# unicorder-mk-1_3-base.net
KiCad netlist of a schematic drawn in EAGLE
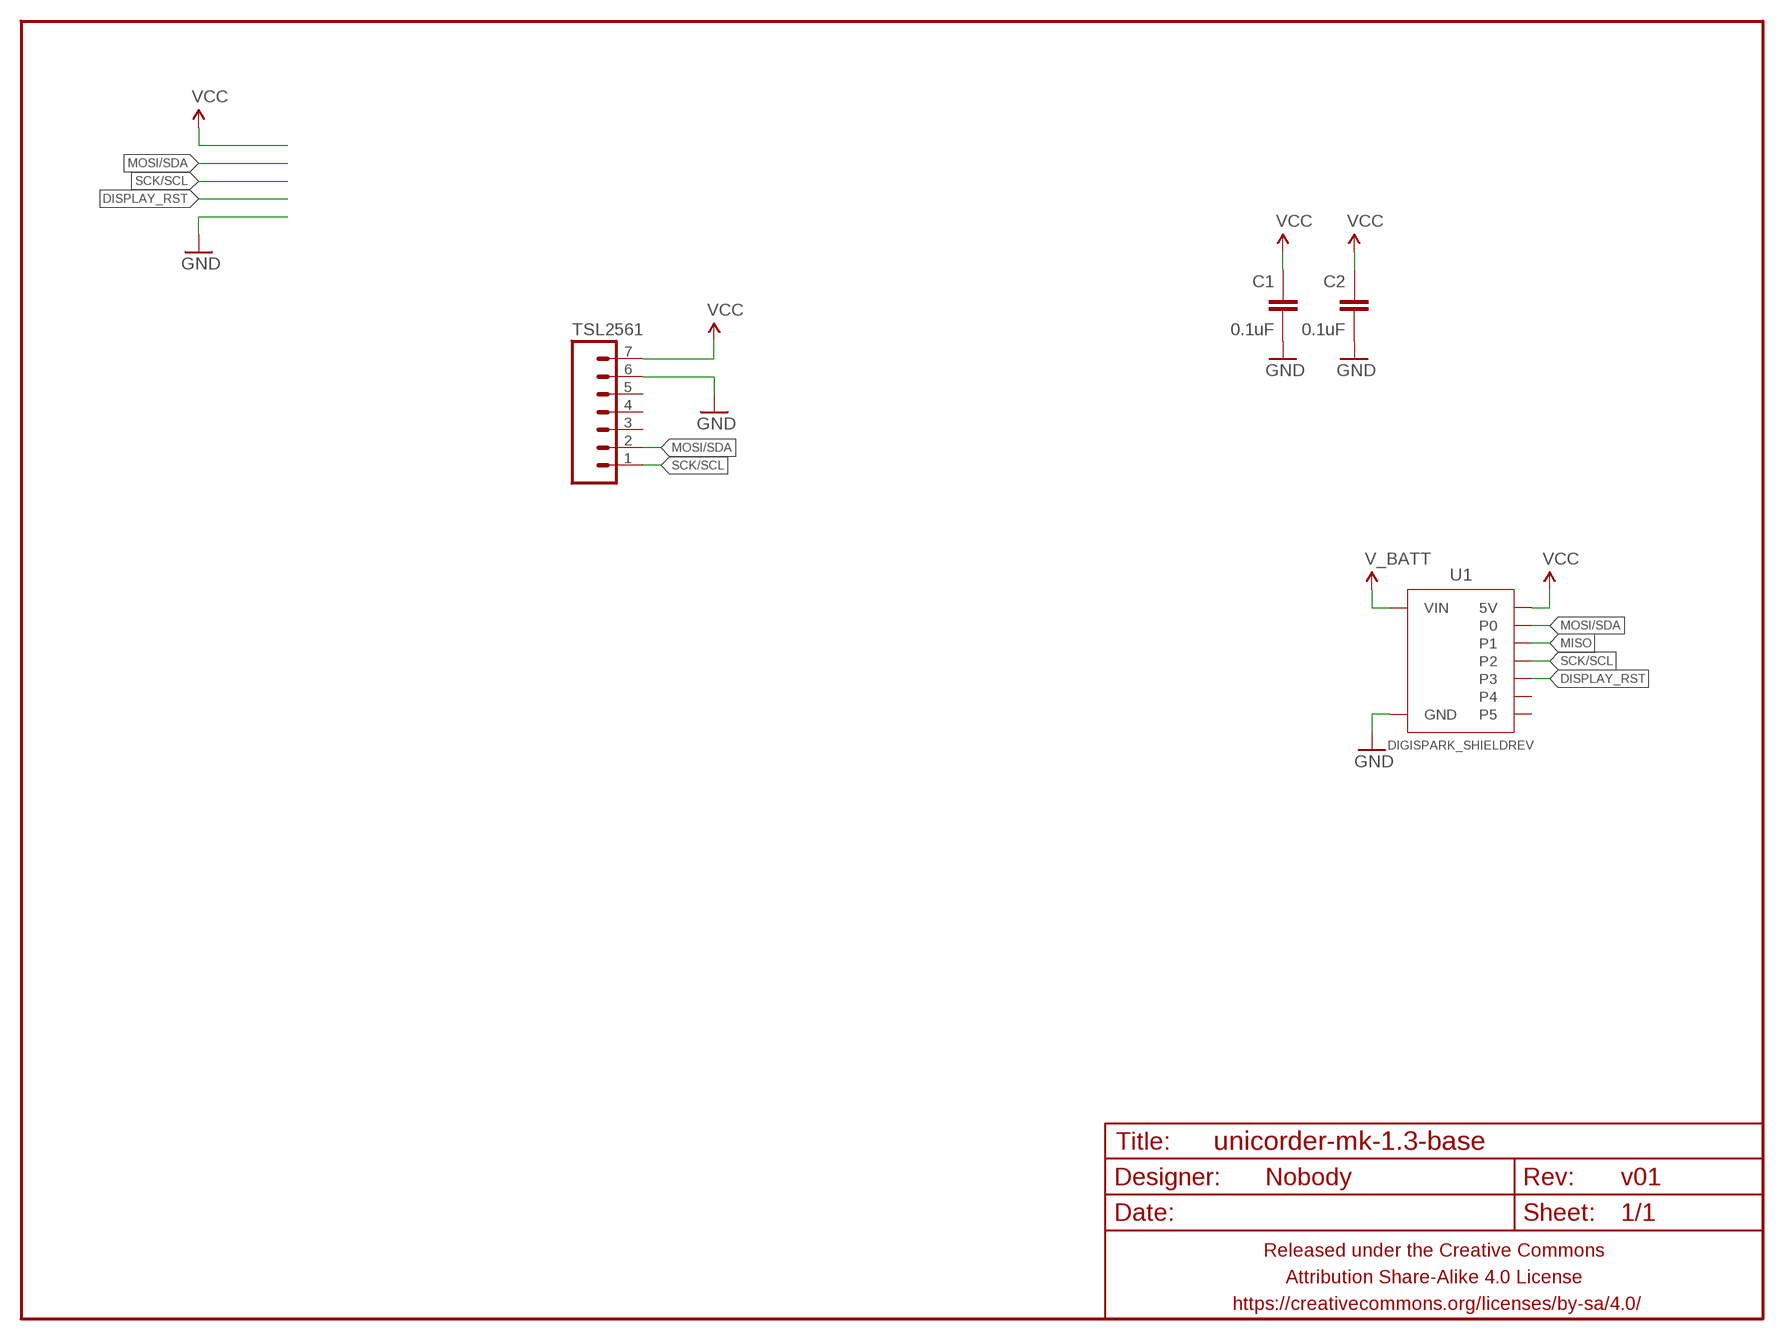
[diagram p0: schematic, sheet 1]

(export (version "E")
  (design (tool "Eeschema 10.0.6"))
  (components
    (comp (ref "C1")
      (value "0.1uF")
      (footprint "eagle-import:C025-024X044")
      (libsource (lib "eagle-import") (part "CAPACITOR-CERAMIC025-024X044"))
    )
    (comp (ref "C2")
      (value "0.1uF")
      (footprint "eagle-import:C025-024X044")
      (libsource (lib "eagle-import") (part "CAPACITOR-CERAMIC025-024X044"))
    )
    (comp (ref "FRAME1")
      (value "FRAME-LETTERNO_PACKAGE")
      (footprint "eagle-import:DUMMY")
      (fields (field (name "DESIGNER") "Nobody"))
      (libsource (lib "eagle-import") (part "FRAME-LETTERNO_PACKAGE"))
    )
    (comp (ref "TSL2561")
      (value "M07PTH-SLIMASS")
      (footprint "eagle-import:1X07_PTH_SLIMASS")
      (libsource (lib "eagle-import") (part "M07PTH-SLIMASS"))
    )
    (comp (ref "U1")
      (value "DIGISPARK_SHIELDREV")
      (footprint "eagle-import:DIGISPARK_SHIELD_REV")
      (libsource (lib "eagle-import") (part "DIGISPARK_SHIELDREV"))
    )
  )
  (nets
    (net (code "1") (name "DISPLAY_RST") (class "Default")
      (node (ref "U1") (pin "P3") (pinfunction "P3_P3") (pintype "bidirectional"))
    )
    (net (code "2") (name "GND") (class "Default")
      (node (ref "C1") (pin "2") (pinfunction "2_2") (pintype "passive"))
      (node (ref "C2") (pin "2") (pinfunction "2_2") (pintype "passive"))
      (node (ref "TSL2561") (pin "6") (pinfunction "6_6") (pintype "passive"))
      (node (ref "U1") (pin "GND") (pinfunction "GND_GND") (pintype "bidirectional"))
    )
    (net (code "3") (name "MISO") (class "Default")
      (node (ref "U1") (pin "P1") (pinfunction "P1_P1") (pintype "bidirectional"))
    )
    (net (code "4") (name "MOSI{slash}SDA") (class "Default")
      (node (ref "TSL2561") (pin "2") (pinfunction "2_2") (pintype "passive"))
      (node (ref "U1") (pin "P0") (pinfunction "P0_P0") (pintype "bidirectional"))
    )
    (net (code "5") (name "SCK{slash}SCL") (class "Default")
      (node (ref "TSL2561") (pin "1") (pinfunction "1_1") (pintype "passive"))
      (node (ref "U1") (pin "P2") (pinfunction "P2_P2") (pintype "bidirectional"))
    )
    (net (code "6") (name "VCC") (class "Default")
      (node (ref "C1") (pin "1") (pinfunction "1_1") (pintype "passive"))
      (node (ref "C2") (pin "1") (pinfunction "1_1") (pintype "passive"))
      (node (ref "TSL2561") (pin "7") (pinfunction "7_7") (pintype "passive"))
      (node (ref "U1") (pin "5V") (pinfunction "5V_5V") (pintype "bidirectional"))
    )
    (net (code "7") (name "V_BATT") (class "Default")
      (node (ref "U1") (pin "VIN") (pinfunction "VIN_VIN") (pintype "bidirectional"))
    )
    (net (code "8") (name "unconnected-(TSL2561-Pad3)") (class "Default")
      (node (ref "TSL2561") (pin "3") (pinfunction "3_3") (pintype "passive"))
    )
    (net (code "9") (name "unconnected-(TSL2561-Pad4)") (class "Default")
      (node (ref "TSL2561") (pin "4") (pinfunction "4_4") (pintype "passive"))
    )
    (net (code "10") (name "unconnected-(TSL2561-Pad5)") (class "Default")
      (node (ref "TSL2561") (pin "5") (pinfunction "5_5") (pintype "passive"))
    )
    (net (code "11") (name "unconnected-(U1-PadP4)") (class "Default")
      (node (ref "U1") (pin "P4") (pinfunction "P4_P4") (pintype "bidirectional"))
    )
    (net (code "12") (name "unconnected-(U1-PadP5)") (class "Default")
      (node (ref "U1") (pin "P5") (pinfunction "P5_P5") (pintype "bidirectional"))
    )
  )
)
